# wisleep_dbg_revB.net
KiCad netlist of a schematic drawn in EAGLE
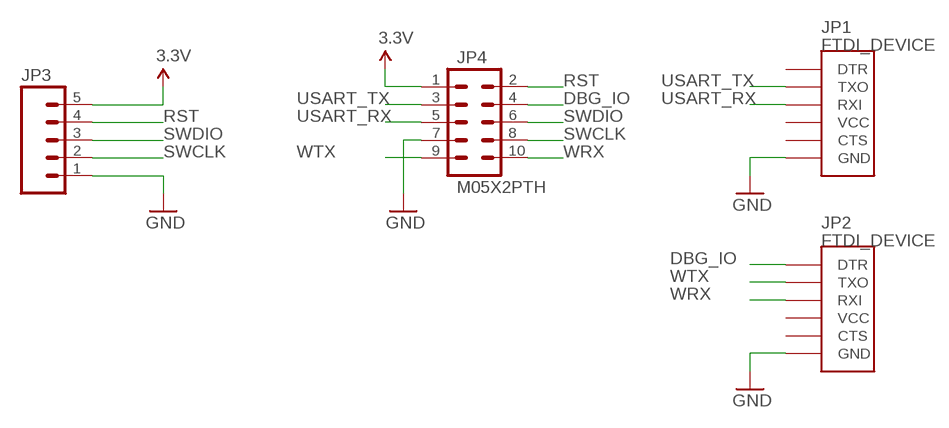
[diagram p0: schematic, sheet 1]

(export (version "E")
  (design (tool "Eeschema 10.0.6"))
  (components
    (comp (ref "JP1")
      (value "FTDI_DEVICE")
      (footprint "eagle-import:FTDI_DEVICE_SIDE")
      (libsource (lib "eagle-import") (part "FTDI_DEVICE"))
    )
    (comp (ref "JP2")
      (value "FTDI_DEVICE")
      (footprint "eagle-import:FTDI_DEVICE_SIDE")
      (libsource (lib "eagle-import") (part "FTDI_DEVICE"))
    )
    (comp (ref "JP3")
      (value "M05LOCK")
      (footprint "eagle-import:1X05_LOCK")
      (libsource (lib "eagle-import") (part "M05LOCK"))
    )
    (comp (ref "JP4")
      (value "M05X2PTH")
      (footprint "eagle-import:AVR_ICSP")
      (libsource (lib "eagle-import") (part "M05X2PTH"))
    )
  )
  (nets
    (net (code "1") (name "/DBG_IO") (class "Default")
      (node (ref "JP2") (pin "P$1") (pinfunction "DTR_P$1") (pintype "bidirectional"))
      (node (ref "JP4") (pin "4") (pinfunction "4_4") (pintype "passive"))
    )
    (net (code "2") (name "/RST") (class "Default")
      (node (ref "JP3") (pin "4") (pinfunction "4_4") (pintype "passive"))
      (node (ref "JP4") (pin "2") (pinfunction "2_2") (pintype "passive"))
    )
    (net (code "3") (name "/SWCLK") (class "Default")
      (node (ref "JP3") (pin "2") (pinfunction "2_2") (pintype "passive"))
      (node (ref "JP4") (pin "8") (pinfunction "8_8") (pintype "passive"))
    )
    (net (code "4") (name "/SWDIO") (class "Default")
      (node (ref "JP3") (pin "3") (pinfunction "3_3") (pintype "passive"))
      (node (ref "JP4") (pin "6") (pinfunction "6_6") (pintype "passive"))
    )
    (net (code "5") (name "/USART_RX") (class "Default")
      (node (ref "JP1") (pin "P$3") (pinfunction "RXI_P$3") (pintype "bidirectional"))
      (node (ref "JP4") (pin "5") (pinfunction "5_5") (pintype "passive"))
    )
    (net (code "6") (name "/USART_TX") (class "Default")
      (node (ref "JP1") (pin "P$2") (pinfunction "TXO_P$2") (pintype "bidirectional"))
      (node (ref "JP4") (pin "3") (pinfunction "3_3") (pintype "passive"))
    )
    (net (code "7") (name "/WRX") (class "Default")
      (node (ref "JP2") (pin "P$3") (pinfunction "RXI_P$3") (pintype "bidirectional"))
      (node (ref "JP4") (pin "10") (pinfunction "10_10") (pintype "passive"))
    )
    (net (code "8") (name "/WTX") (class "Default")
      (node (ref "JP2") (pin "P$2") (pinfunction "TXO_P$2") (pintype "bidirectional"))
      (node (ref "JP4") (pin "9") (pinfunction "9_9") (pintype "passive"))
    )
    (net (code "9") (name "3.3V") (class "Default")
      (node (ref "JP3") (pin "5") (pinfunction "5_5") (pintype "passive"))
      (node (ref "JP4") (pin "1") (pinfunction "1_1") (pintype "passive"))
    )
    (net (code "10") (name "GND") (class "Default")
      (node (ref "JP1") (pin "P$6") (pinfunction "GND_P$6") (pintype "bidirectional"))
      (node (ref "JP2") (pin "P$6") (pinfunction "GND_P$6") (pintype "bidirectional"))
      (node (ref "JP3") (pin "1") (pinfunction "1_1") (pintype "passive"))
      (node (ref "JP4") (pin "7") (pinfunction "7_7") (pintype "passive"))
    )
    (net (code "11") (name "unconnected-(JP1-CTS-PadP$5)") (class "Default")
      (node (ref "JP1") (pin "P$5") (pinfunction "CTS_P$5") (pintype "bidirectional"))
    )
    (net (code "12") (name "unconnected-(JP1-DTR-PadP$1)") (class "Default")
      (node (ref "JP1") (pin "P$1") (pinfunction "DTR_P$1") (pintype "bidirectional"))
    )
    (net (code "13") (name "unconnected-(JP1-VCC-PadP$4)") (class "Default")
      (node (ref "JP1") (pin "P$4") (pinfunction "VCC_P$4") (pintype "bidirectional"))
    )
    (net (code "14") (name "unconnected-(JP2-CTS-PadP$5)") (class "Default")
      (node (ref "JP2") (pin "P$5") (pinfunction "CTS_P$5") (pintype "bidirectional"))
    )
    (net (code "15") (name "unconnected-(JP2-VCC-PadP$4)") (class "Default")
      (node (ref "JP2") (pin "P$4") (pinfunction "VCC_P$4") (pintype "bidirectional"))
    )
  )
)
